# microsd-switch.net
KiCad netlist of a schematic drawn in EAGLE
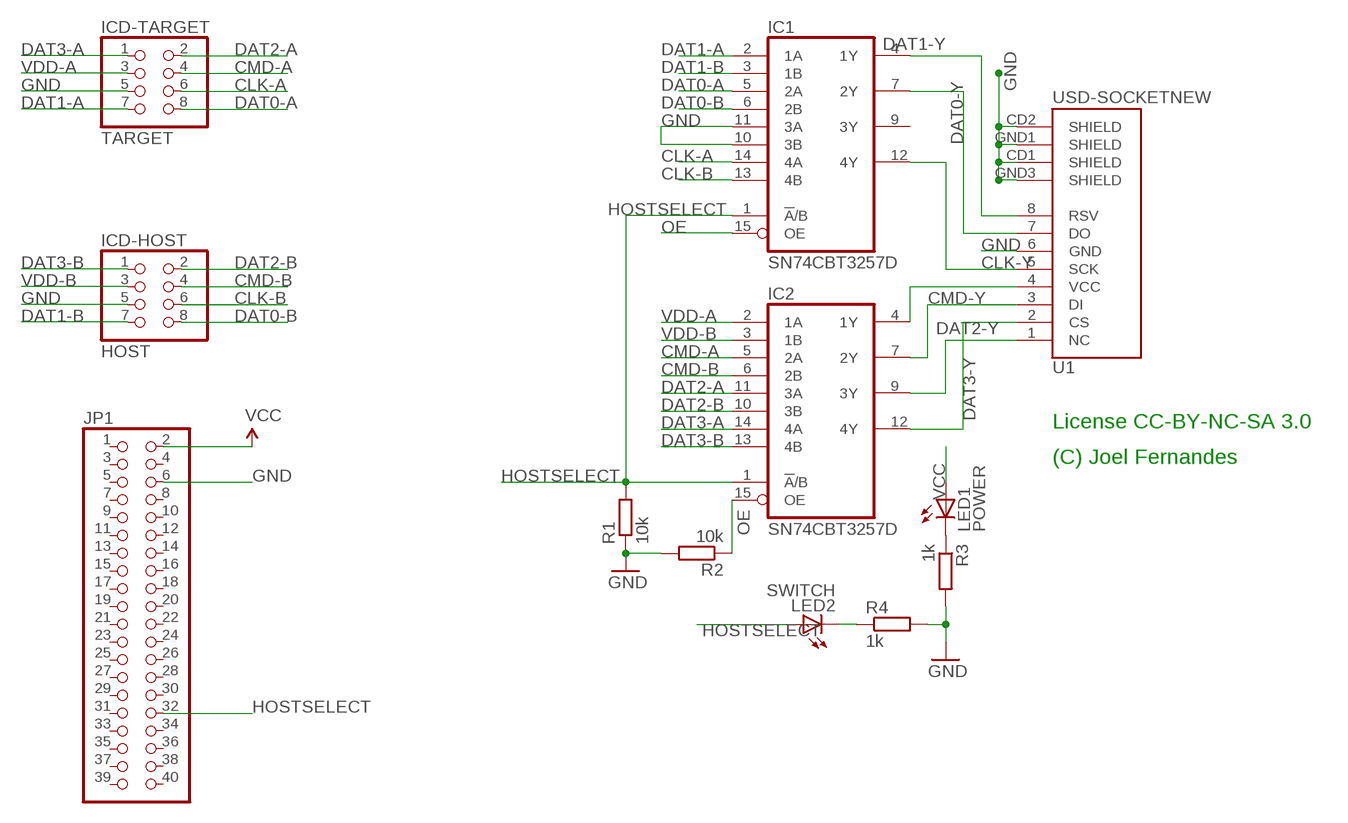
[diagram p0: schematic, sheet 1]

(export (version "E")
  (design (tool "Eeschema 10.0.6"))
  (components
    (comp (ref "IC1")
      (value "SN74CBT3257D")
      (footprint "eagle-import:SO16")
      (libsource (lib "eagle-import") (part "SN74CBT3257D"))
    )
    (comp (ref "IC2")
      (value "SN74CBT3257D")
      (footprint "eagle-import:SO16")
      (libsource (lib "eagle-import") (part "SN74CBT3257D"))
    )
    (comp (ref "ICD-HOST")
      (value "HOST")
      (footprint "eagle-import:2X04")
      (libsource (lib "eagle-import") (part "PINHD-2X4"))
    )
    (comp (ref "ICD-TARGET")
      (value "TARGET")
      (footprint "eagle-import:2X04")
      (libsource (lib "eagle-import") (part "PINHD-2X4"))
    )
    (comp (ref "JP1")
      (value "PINHD-2X20")
      (footprint "eagle-import:2X20")
      (libsource (lib "eagle-import") (part "PINHD-2X20"))
    )
    (comp (ref "LED1")
      (value "POWER")
      (footprint "eagle-import:CHIP-LED0805")
      (libsource (lib "eagle-import") (part "LEDCHIP-LED0805"))
    )
    (comp (ref "LED2")
      (value "SWITCH")
      (footprint "eagle-import:CHIP-LED0805")
      (libsource (lib "eagle-import") (part "LEDCHIP-LED0805"))
    )
    (comp (ref "R1")
      (value "10k")
      (footprint "eagle-import:R1206")
      (libsource (lib "eagle-import") (part "R-EU_R1206"))
    )
    (comp (ref "R2")
      (value "10k")
      (footprint "eagle-import:R1206")
      (libsource (lib "eagle-import") (part "R-EU_R1206"))
    )
    (comp (ref "R3")
      (value "1k")
      (footprint "eagle-import:R1206")
      (libsource (lib "eagle-import") (part "R-EU_R1206"))
    )
    (comp (ref "R4")
      (value "1k")
      (footprint "eagle-import:R1206")
      (libsource (lib "eagle-import") (part "R-EU_R1206"))
    )
    (comp (ref "U1")
      (value "USD-SOCKETNEW")
      (footprint "eagle-import:MICRO-SD-SOCKET-PP")
      (libsource (lib "eagle-import") (part "USD-SOCKETNEW"))
    )
  )
  (nets
    (net (code "1") (name "/CLK-A") (class "Default")
      (node (ref "IC1") (pin "14") (pinfunction "4A_14") (pintype "input"))
      (node (ref "ICD-TARGET") (pin "6") (pinfunction "6_6") (pintype "passive"))
    )
    (net (code "2") (name "/CLK-B") (class "Default")
      (node (ref "IC1") (pin "13") (pinfunction "4B_13") (pintype "input"))
      (node (ref "ICD-HOST") (pin "6") (pinfunction "6_6") (pintype "passive"))
    )
    (net (code "3") (name "/CLK-Y") (class "Default")
      (node (ref "IC1") (pin "12") (pinfunction "4Y_12") (pintype "output"))
      (node (ref "U1") (pin "5") (pinfunction "SCK_5") (pintype "bidirectional"))
    )
    (net (code "4") (name "/CMD-A") (class "Default")
      (node (ref "IC2") (pin "5") (pinfunction "2A_5") (pintype "input"))
      (node (ref "ICD-TARGET") (pin "4") (pinfunction "4_4") (pintype "passive"))
    )
    (net (code "5") (name "/CMD-B") (class "Default")
      (node (ref "IC2") (pin "6") (pinfunction "2B_6") (pintype "input"))
      (node (ref "ICD-HOST") (pin "4") (pinfunction "4_4") (pintype "passive"))
    )
    (net (code "6") (name "/CMD-Y") (class "Default")
      (node (ref "IC2") (pin "7") (pinfunction "2Y_7") (pintype "output"))
      (node (ref "U1") (pin "3") (pinfunction "DI_3") (pintype "bidirectional"))
    )
    (net (code "7") (name "/DAT0-A") (class "Default")
      (node (ref "IC1") (pin "5") (pinfunction "2A_5") (pintype "input"))
      (node (ref "ICD-TARGET") (pin "8") (pinfunction "8_8") (pintype "passive"))
    )
    (net (code "8") (name "/DAT0-B") (class "Default")
      (node (ref "IC1") (pin "6") (pinfunction "2B_6") (pintype "input"))
      (node (ref "ICD-HOST") (pin "8") (pinfunction "8_8") (pintype "passive"))
    )
    (net (code "9") (name "/DAT0-Y") (class "Default")
      (node (ref "IC1") (pin "7") (pinfunction "2Y_7") (pintype "output"))
      (node (ref "U1") (pin "7") (pinfunction "DO_7") (pintype "bidirectional"))
    )
    (net (code "10") (name "/DAT1-A") (class "Default")
      (node (ref "IC1") (pin "2") (pinfunction "1A_2") (pintype "input"))
      (node (ref "ICD-TARGET") (pin "7") (pinfunction "7_7") (pintype "passive"))
    )
    (net (code "11") (name "/DAT1-B") (class "Default")
      (node (ref "IC1") (pin "3") (pinfunction "1B_3") (pintype "input"))
      (node (ref "ICD-HOST") (pin "7") (pinfunction "7_7") (pintype "passive"))
    )
    (net (code "12") (name "/DAT1-Y") (class "Default")
      (node (ref "IC1") (pin "4") (pinfunction "1Y_4") (pintype "output"))
      (node (ref "U1") (pin "8") (pinfunction "RSV_8") (pintype "bidirectional"))
    )
    (net (code "13") (name "/DAT2-A") (class "Default")
      (node (ref "IC2") (pin "11") (pinfunction "3A_11") (pintype "input"))
      (node (ref "ICD-TARGET") (pin "2") (pinfunction "2_2") (pintype "passive"))
    )
    (net (code "14") (name "/DAT2-B") (class "Default")
      (node (ref "IC2") (pin "10") (pinfunction "3B_10") (pintype "input"))
      (node (ref "ICD-HOST") (pin "2") (pinfunction "2_2") (pintype "passive"))
    )
    (net (code "15") (name "/DAT2-Y") (class "Default")
      (node (ref "IC2") (pin "9") (pinfunction "3Y_9") (pintype "output"))
      (node (ref "U1") (pin "1") (pinfunction "NC_1") (pintype "bidirectional"))
    )
    (net (code "16") (name "/DAT3-A") (class "Default")
      (node (ref "IC2") (pin "14") (pinfunction "4A_14") (pintype "input"))
      (node (ref "ICD-TARGET") (pin "1") (pinfunction "1_1") (pintype "passive"))
    )
    (net (code "17") (name "/DAT3-B") (class "Default")
      (node (ref "IC2") (pin "13") (pinfunction "4B_13") (pintype "input"))
      (node (ref "ICD-HOST") (pin "1") (pinfunction "1_1") (pintype "passive"))
    )
    (net (code "18") (name "/DAT3-Y") (class "Default")
      (node (ref "IC2") (pin "12") (pinfunction "4Y_12") (pintype "output"))
      (node (ref "U1") (pin "2") (pinfunction "CS_2") (pintype "bidirectional"))
    )
    (net (code "19") (name "/HOSTSELECT") (class "Default")
      (node (ref "IC1") (pin "1") (pinfunction "~{A}/B_1") (pintype "input"))
      (node (ref "IC2") (pin "1") (pinfunction "~{A}/B_1") (pintype "input"))
      (node (ref "JP1") (pin "32") (pinfunction "32_32") (pintype "passive"))
      (node (ref "LED2") (pin "A") (pinfunction "A_A") (pintype "passive"))
      (node (ref "R1") (pin "2") (pinfunction "2_2") (pintype "passive"))
    )
    (net (code "20") (name "/OE") (class "Default")
      (node (ref "IC1") (pin "15") (pinfunction "OE_15") (pintype "input"))
      (node (ref "IC2") (pin "15") (pinfunction "OE_15") (pintype "input"))
      (node (ref "R2") (pin "1") (pinfunction "1_1") (pintype "passive"))
    )
    (net (code "21") (name "/VDD-A") (class "Default")
      (node (ref "IC2") (pin "2") (pinfunction "1A_2") (pintype "input"))
      (node (ref "ICD-TARGET") (pin "3") (pinfunction "3_3") (pintype "passive"))
    )
    (net (code "22") (name "/VDD-B") (class "Default")
      (node (ref "IC2") (pin "3") (pinfunction "1B_3") (pintype "input"))
      (node (ref "ICD-HOST") (pin "3") (pinfunction "3_3") (pintype "passive"))
    )
    (net (code "23") (name "GND") (class "Default")
      (node (ref "IC1") (pin "10") (pinfunction "3B_10") (pintype "input"))
      (node (ref "IC1") (pin "11") (pinfunction "3A_11") (pintype "input"))
      (node (ref "ICD-HOST") (pin "5") (pinfunction "5_5") (pintype "passive"))
      (node (ref "ICD-TARGET") (pin "5") (pinfunction "5_5") (pintype "passive"))
      (node (ref "JP1") (pin "6") (pinfunction "6_6") (pintype "passive"))
      (node (ref "R1") (pin "1") (pinfunction "1_1") (pintype "passive"))
      (node (ref "R2") (pin "2") (pinfunction "2_2") (pintype "passive"))
      (node (ref "R3") (pin "2") (pinfunction "2_2") (pintype "passive"))
      (node (ref "R4") (pin "2") (pinfunction "2_2") (pintype "passive"))
      (node (ref "U1") (pin "6") (pinfunction "GND_6") (pintype "bidirectional"))
      (node (ref "U1") (pin "CD1") (pinfunction "SHIELD_CD1") (pintype "bidirectional"))
      (node (ref "U1") (pin "CD2") (pinfunction "SHIELD_CD2") (pintype "bidirectional"))
      (node (ref "U1") (pin "GND1") (pinfunction "SHIELD_GND1") (pintype "bidirectional"))
      (node (ref "U1") (pin "GND3") (pinfunction "SHIELD_GND3") (pintype "bidirectional"))
    )
    (net (code "24") (name "Net-(IC2A-1Y)") (class "Default")
      (node (ref "IC2") (pin "4") (pinfunction "1Y_4") (pintype "output"))
      (node (ref "U1") (pin "4") (pinfunction "VCC_4") (pintype "bidirectional"))
    )
    (net (code "25") (name "Net-(LED1-PadC)") (class "Default")
      (node (ref "LED1") (pin "C") (pinfunction "C_C") (pintype "passive"))
      (node (ref "R3") (pin "1") (pinfunction "1_1") (pintype "passive"))
    )
    (net (code "26") (name "Net-(LED2-PadC)") (class "Default")
      (node (ref "LED2") (pin "C") (pinfunction "C_C") (pintype "passive"))
      (node (ref "R4") (pin "1") (pinfunction "1_1") (pintype "passive"))
    )
    (net (code "27") (name "VCC") (class "Default")
      (node (ref "JP1") (pin "2") (pinfunction "2_2") (pintype "passive"))
      (node (ref "LED1") (pin "A") (pinfunction "A_A") (pintype "passive"))
    )
    (net (code "28") (name "unconnected-(IC1A-3Y-Pad9)") (class "Default")
      (node (ref "IC1") (pin "9") (pinfunction "3Y_9") (pintype "output"))
    )
    (net (code "29") (name "unconnected-(JP1-Pad1)") (class "Default")
      (node (ref "JP1") (pin "1") (pinfunction "1_1") (pintype "passive"))
    )
    (net (code "30") (name "unconnected-(JP1-Pad3)") (class "Default")
      (node (ref "JP1") (pin "3") (pinfunction "3_3") (pintype "passive"))
    )
    (net (code "31") (name "unconnected-(JP1-Pad4)") (class "Default")
      (node (ref "JP1") (pin "4") (pinfunction "4_4") (pintype "passive"))
    )
    (net (code "32") (name "unconnected-(JP1-Pad5)") (class "Default")
      (node (ref "JP1") (pin "5") (pinfunction "5_5") (pintype "passive"))
    )
    (net (code "33") (name "unconnected-(JP1-Pad7)") (class "Default")
      (node (ref "JP1") (pin "7") (pinfunction "7_7") (pintype "passive"))
    )
    (net (code "34") (name "unconnected-(JP1-Pad8)") (class "Default")
      (node (ref "JP1") (pin "8") (pinfunction "8_8") (pintype "passive"))
    )
    (net (code "35") (name "unconnected-(JP1-Pad9)") (class "Default")
      (node (ref "JP1") (pin "9") (pinfunction "9_9") (pintype "passive"))
    )
    (net (code "36") (name "unconnected-(JP1-Pad10)") (class "Default")
      (node (ref "JP1") (pin "10") (pinfunction "10_10") (pintype "passive"))
    )
    (net (code "37") (name "unconnected-(JP1-Pad11)") (class "Default")
      (node (ref "JP1") (pin "11") (pinfunction "11_11") (pintype "passive"))
    )
    (net (code "38") (name "unconnected-(JP1-Pad12)") (class "Default")
      (node (ref "JP1") (pin "12") (pinfunction "12_12") (pintype "passive"))
    )
    (net (code "39") (name "unconnected-(JP1-Pad13)") (class "Default")
      (node (ref "JP1") (pin "13") (pinfunction "13_13") (pintype "passive"))
    )
    (net (code "40") (name "unconnected-(JP1-Pad14)") (class "Default")
      (node (ref "JP1") (pin "14") (pinfunction "14_14") (pintype "passive"))
    )
    (net (code "41") (name "unconnected-(JP1-Pad15)") (class "Default")
      (node (ref "JP1") (pin "15") (pinfunction "15_15") (pintype "passive"))
    )
    (net (code "42") (name "unconnected-(JP1-Pad16)") (class "Default")
      (node (ref "JP1") (pin "16") (pinfunction "16_16") (pintype "passive"))
    )
    (net (code "43") (name "unconnected-(JP1-Pad17)") (class "Default")
      (node (ref "JP1") (pin "17") (pinfunction "17_17") (pintype "passive"))
    )
    (net (code "44") (name "unconnected-(JP1-Pad18)") (class "Default")
      (node (ref "JP1") (pin "18") (pinfunction "18_18") (pintype "passive"))
    )
    (net (code "45") (name "unconnected-(JP1-Pad19)") (class "Default")
      (node (ref "JP1") (pin "19") (pinfunction "19_19") (pintype "passive"))
    )
    (net (code "46") (name "unconnected-(JP1-Pad20)") (class "Default")
      (node (ref "JP1") (pin "20") (pinfunction "20_20") (pintype "passive"))
    )
    (net (code "47") (name "unconnected-(JP1-Pad21)") (class "Default")
      (node (ref "JP1") (pin "21") (pinfunction "21_21") (pintype "passive"))
    )
    (net (code "48") (name "unconnected-(JP1-Pad22)") (class "Default")
      (node (ref "JP1") (pin "22") (pinfunction "22_22") (pintype "passive"))
    )
    (net (code "49") (name "unconnected-(JP1-Pad23)") (class "Default")
      (node (ref "JP1") (pin "23") (pinfunction "23_23") (pintype "passive"))
    )
    (net (code "50") (name "unconnected-(JP1-Pad24)") (class "Default")
      (node (ref "JP1") (pin "24") (pinfunction "24_24") (pintype "passive"))
    )
    (net (code "51") (name "unconnected-(JP1-Pad25)") (class "Default")
      (node (ref "JP1") (pin "25") (pinfunction "25_25") (pintype "passive"))
    )
    (net (code "52") (name "unconnected-(JP1-Pad26)") (class "Default")
      (node (ref "JP1") (pin "26") (pinfunction "26_26") (pintype "passive"))
    )
    (net (code "53") (name "unconnected-(JP1-Pad27)") (class "Default")
      (node (ref "JP1") (pin "27") (pinfunction "27_27") (pintype "passive"))
    )
    (net (code "54") (name "unconnected-(JP1-Pad28)") (class "Default")
      (node (ref "JP1") (pin "28") (pinfunction "28_28") (pintype "passive"))
    )
    (net (code "55") (name "unconnected-(JP1-Pad29)") (class "Default")
      (node (ref "JP1") (pin "29") (pinfunction "29_29") (pintype "passive"))
    )
    (net (code "56") (name "unconnected-(JP1-Pad30)") (class "Default")
      (node (ref "JP1") (pin "30") (pinfunction "30_30") (pintype "passive"))
    )
    (net (code "57") (name "unconnected-(JP1-Pad31)") (class "Default")
      (node (ref "JP1") (pin "31") (pinfunction "31_31") (pintype "passive"))
    )
    (net (code "58") (name "unconnected-(JP1-Pad33)") (class "Default")
      (node (ref "JP1") (pin "33") (pinfunction "33_33") (pintype "passive"))
    )
    (net (code "59") (name "unconnected-(JP1-Pad34)") (class "Default")
      (node (ref "JP1") (pin "34") (pinfunction "34_34") (pintype "passive"))
    )
    (net (code "60") (name "unconnected-(JP1-Pad35)") (class "Default")
      (node (ref "JP1") (pin "35") (pinfunction "35_35") (pintype "passive"))
    )
    (net (code "61") (name "unconnected-(JP1-Pad36)") (class "Default")
      (node (ref "JP1") (pin "36") (pinfunction "36_36") (pintype "passive"))
    )
    (net (code "62") (name "unconnected-(JP1-Pad37)") (class "Default")
      (node (ref "JP1") (pin "37") (pinfunction "37_37") (pintype "passive"))
    )
    (net (code "63") (name "unconnected-(JP1-Pad38)") (class "Default")
      (node (ref "JP1") (pin "38") (pinfunction "38_38") (pintype "passive"))
    )
    (net (code "64") (name "unconnected-(JP1-Pad39)") (class "Default")
      (node (ref "JP1") (pin "39") (pinfunction "39_39") (pintype "passive"))
    )
    (net (code "65") (name "unconnected-(JP1-Pad40)") (class "Default")
      (node (ref "JP1") (pin "40") (pinfunction "40_40") (pintype "passive"))
    )
  )
)
